# ASM001-design-2.net
KiCad netlist of a schematic drawn in Altium Designer
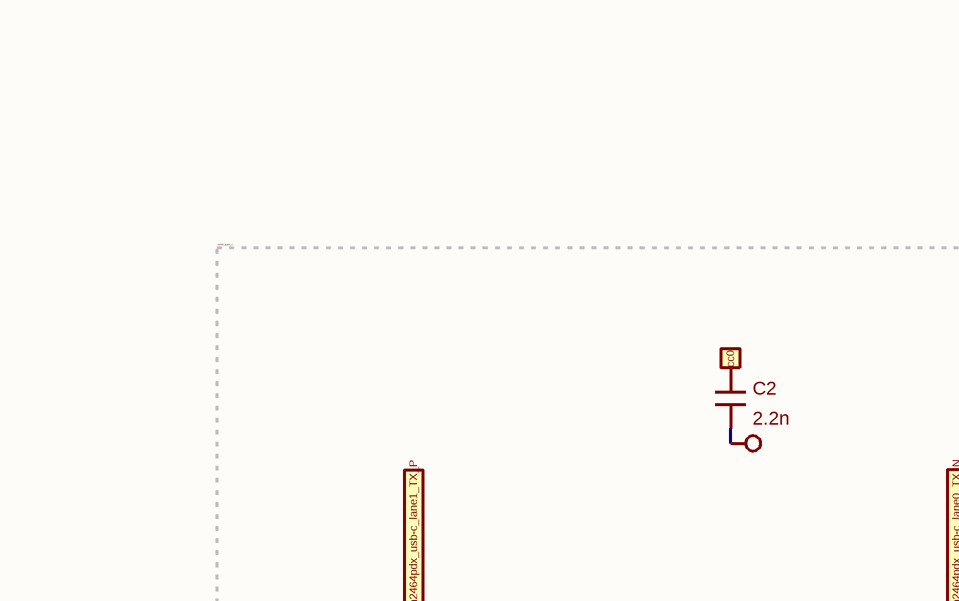
[diagram p0: ASM001-design-2.SchDoc, top column 1 of 4]
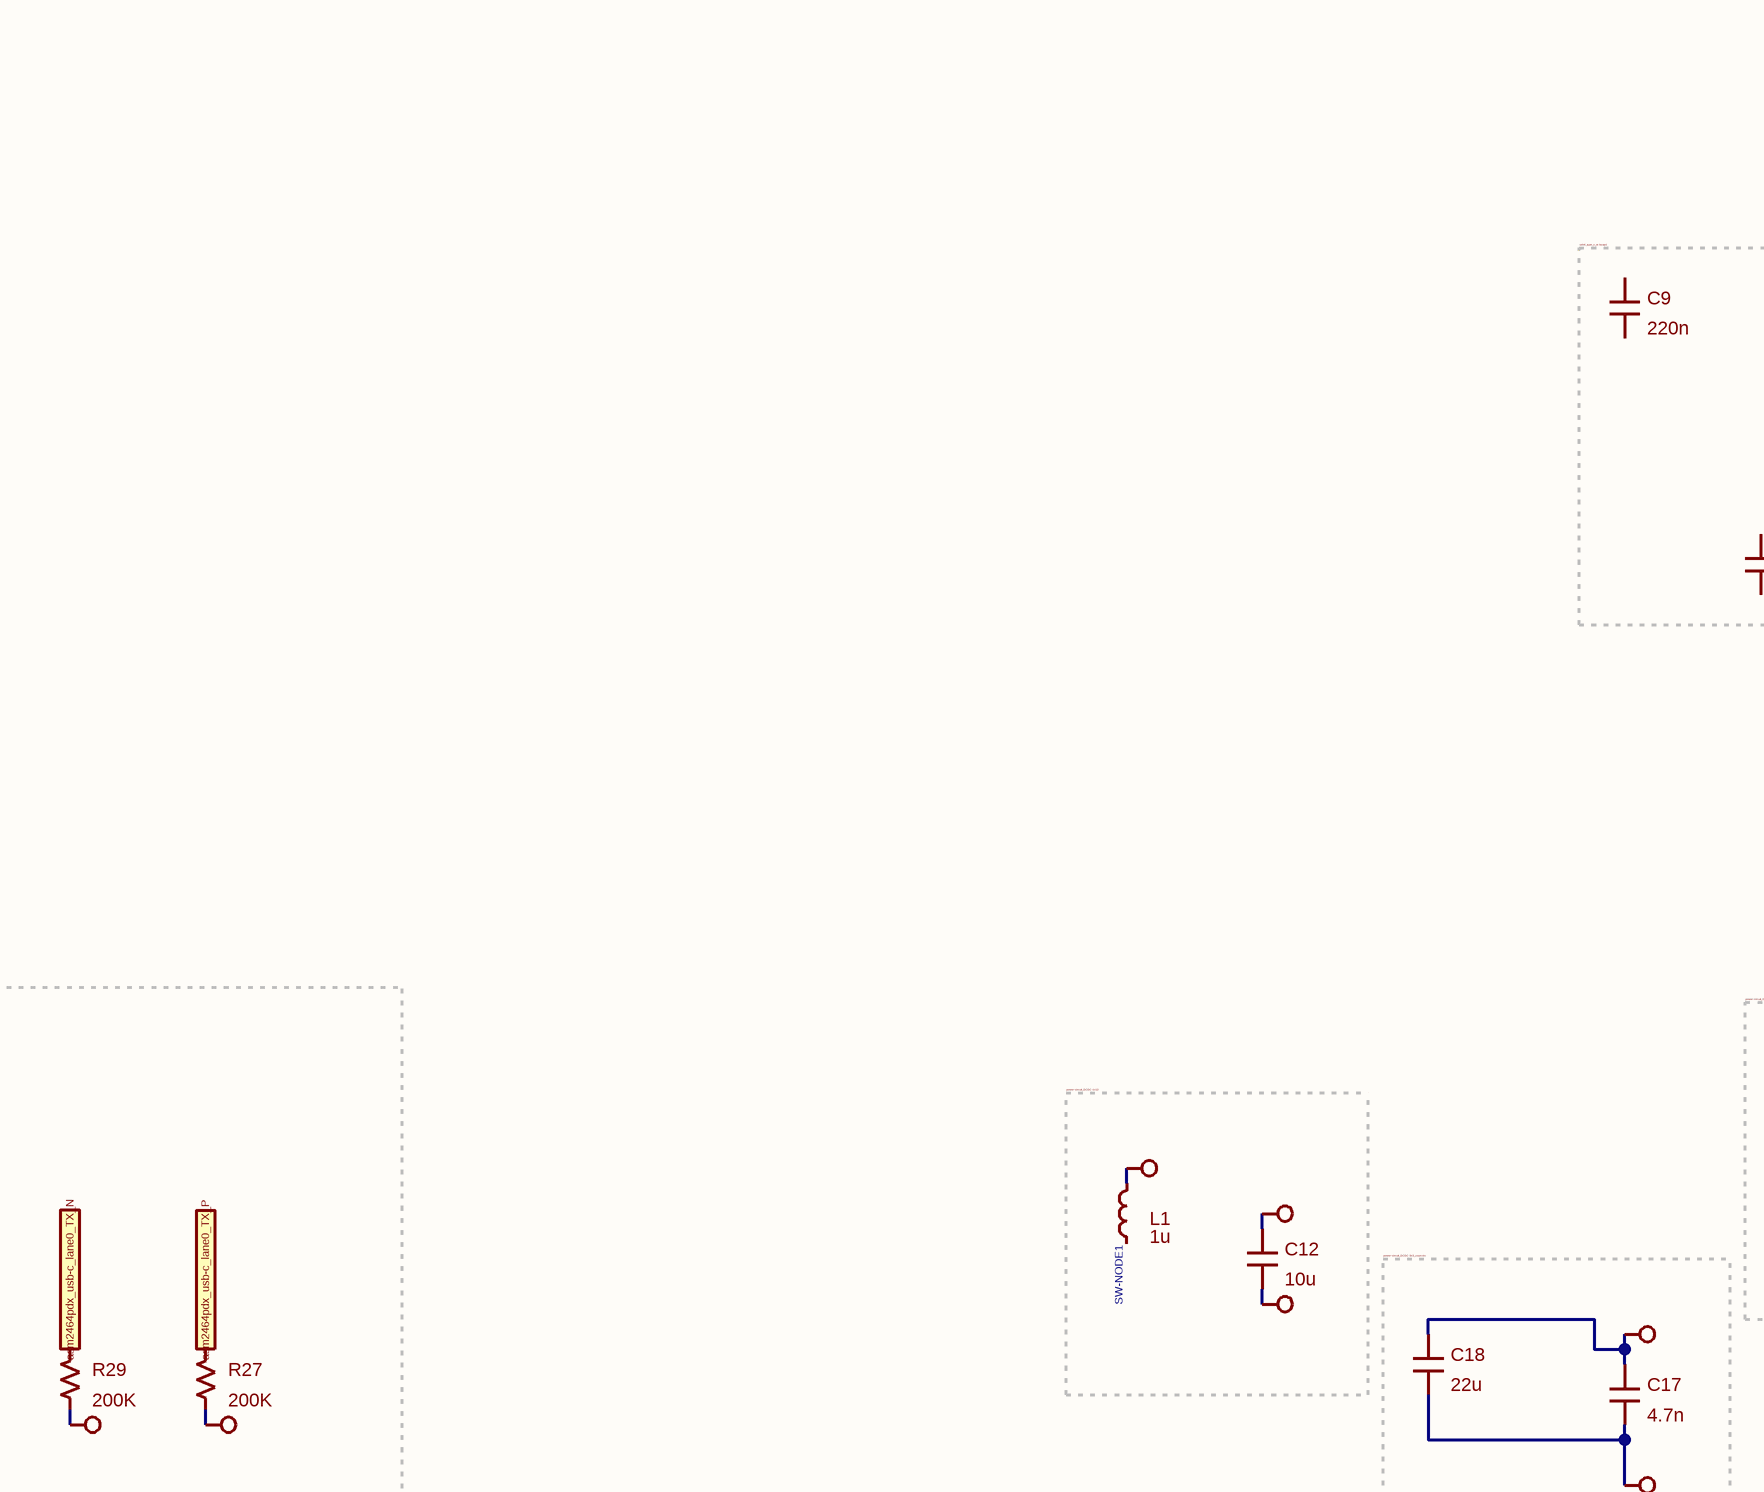
[diagram p1: ASM001-design-2.SchDoc, top column 2 of 4]
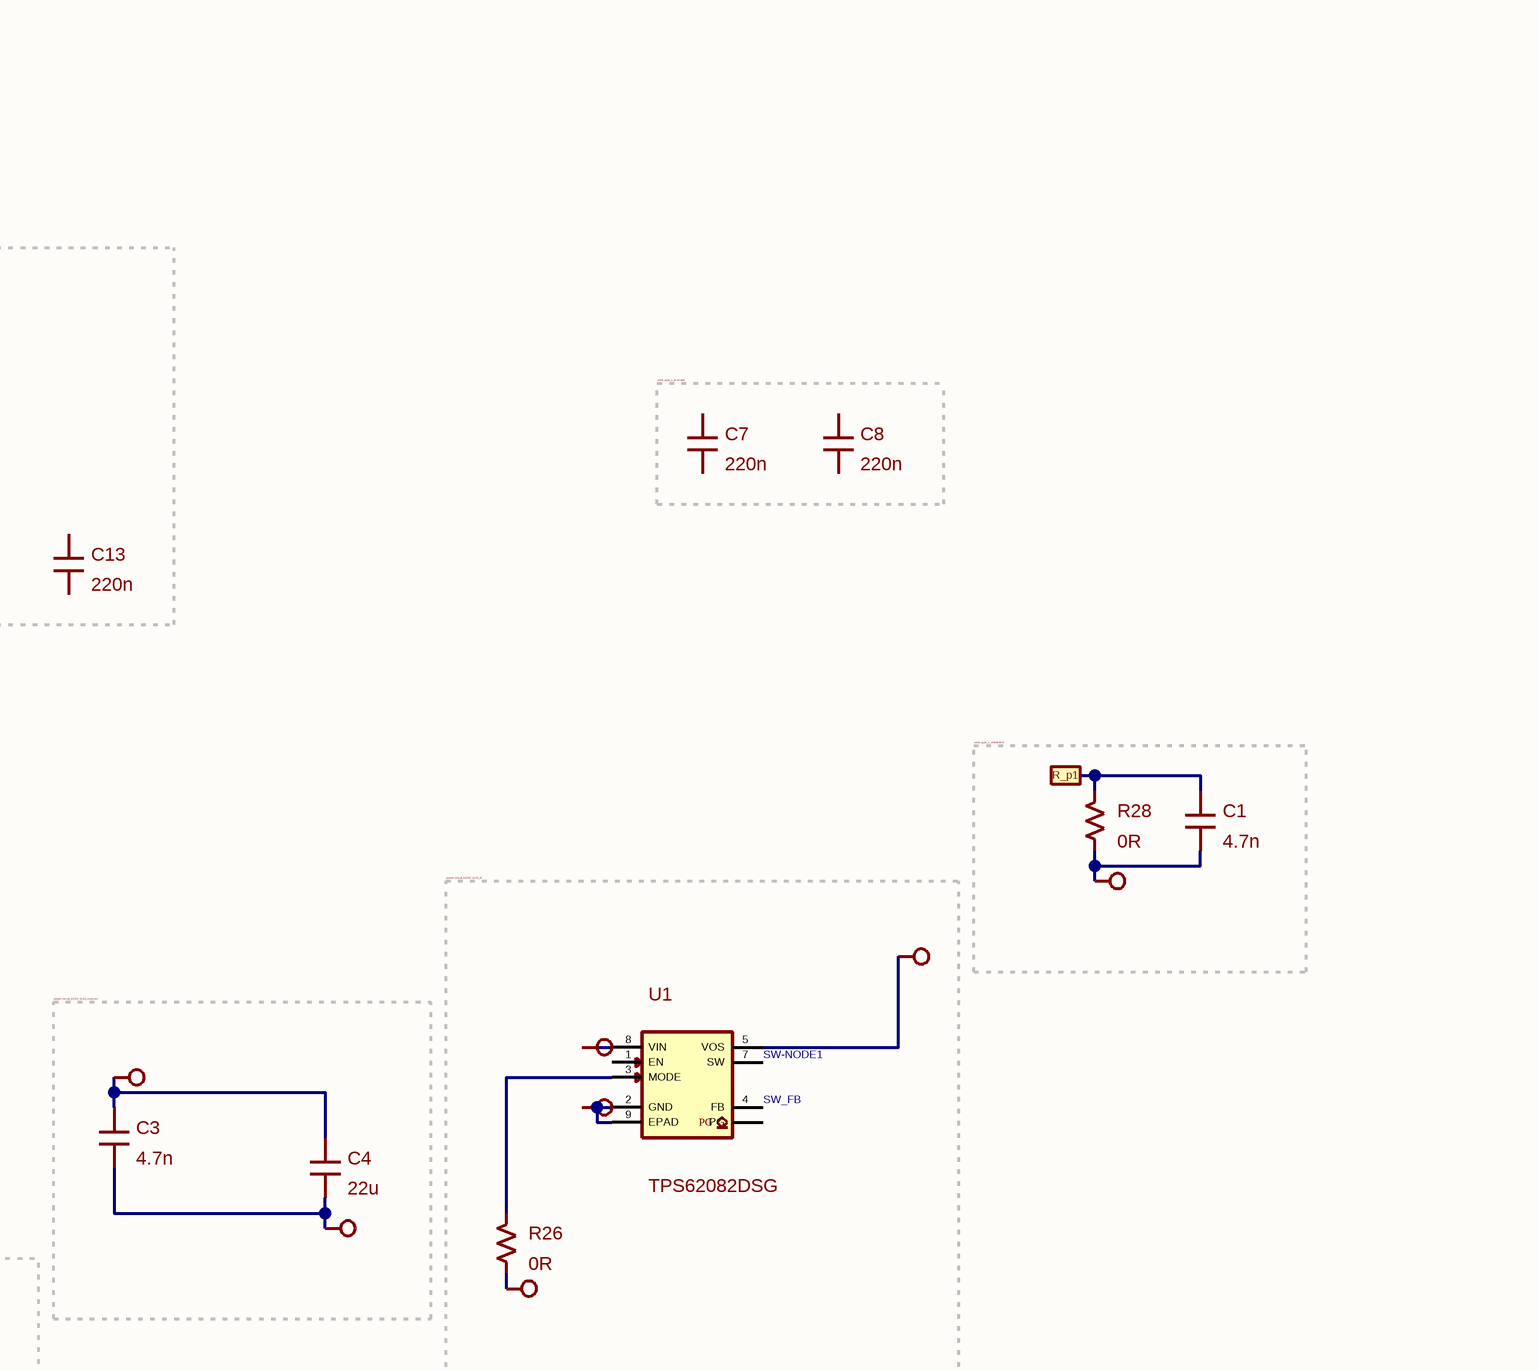
[diagram p2: ASM001-design-2.SchDoc, top column 3 of 4]
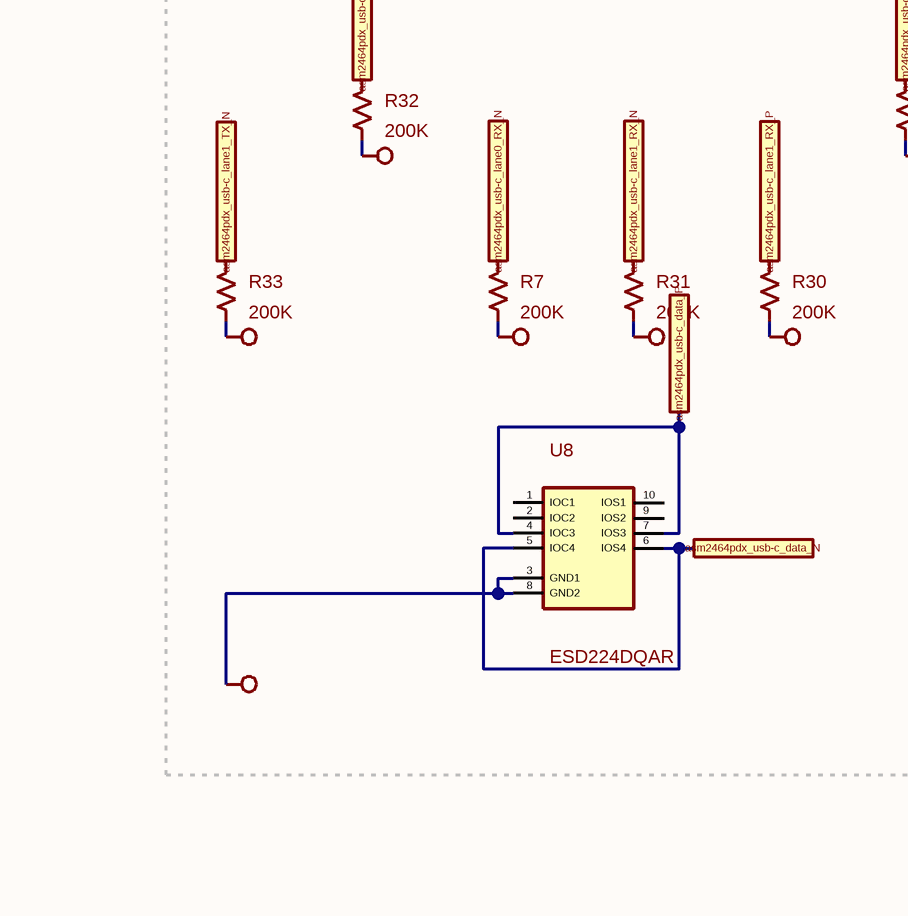
[diagram p3: ASM001-design-2.SchDoc, centre column 1 of 4]
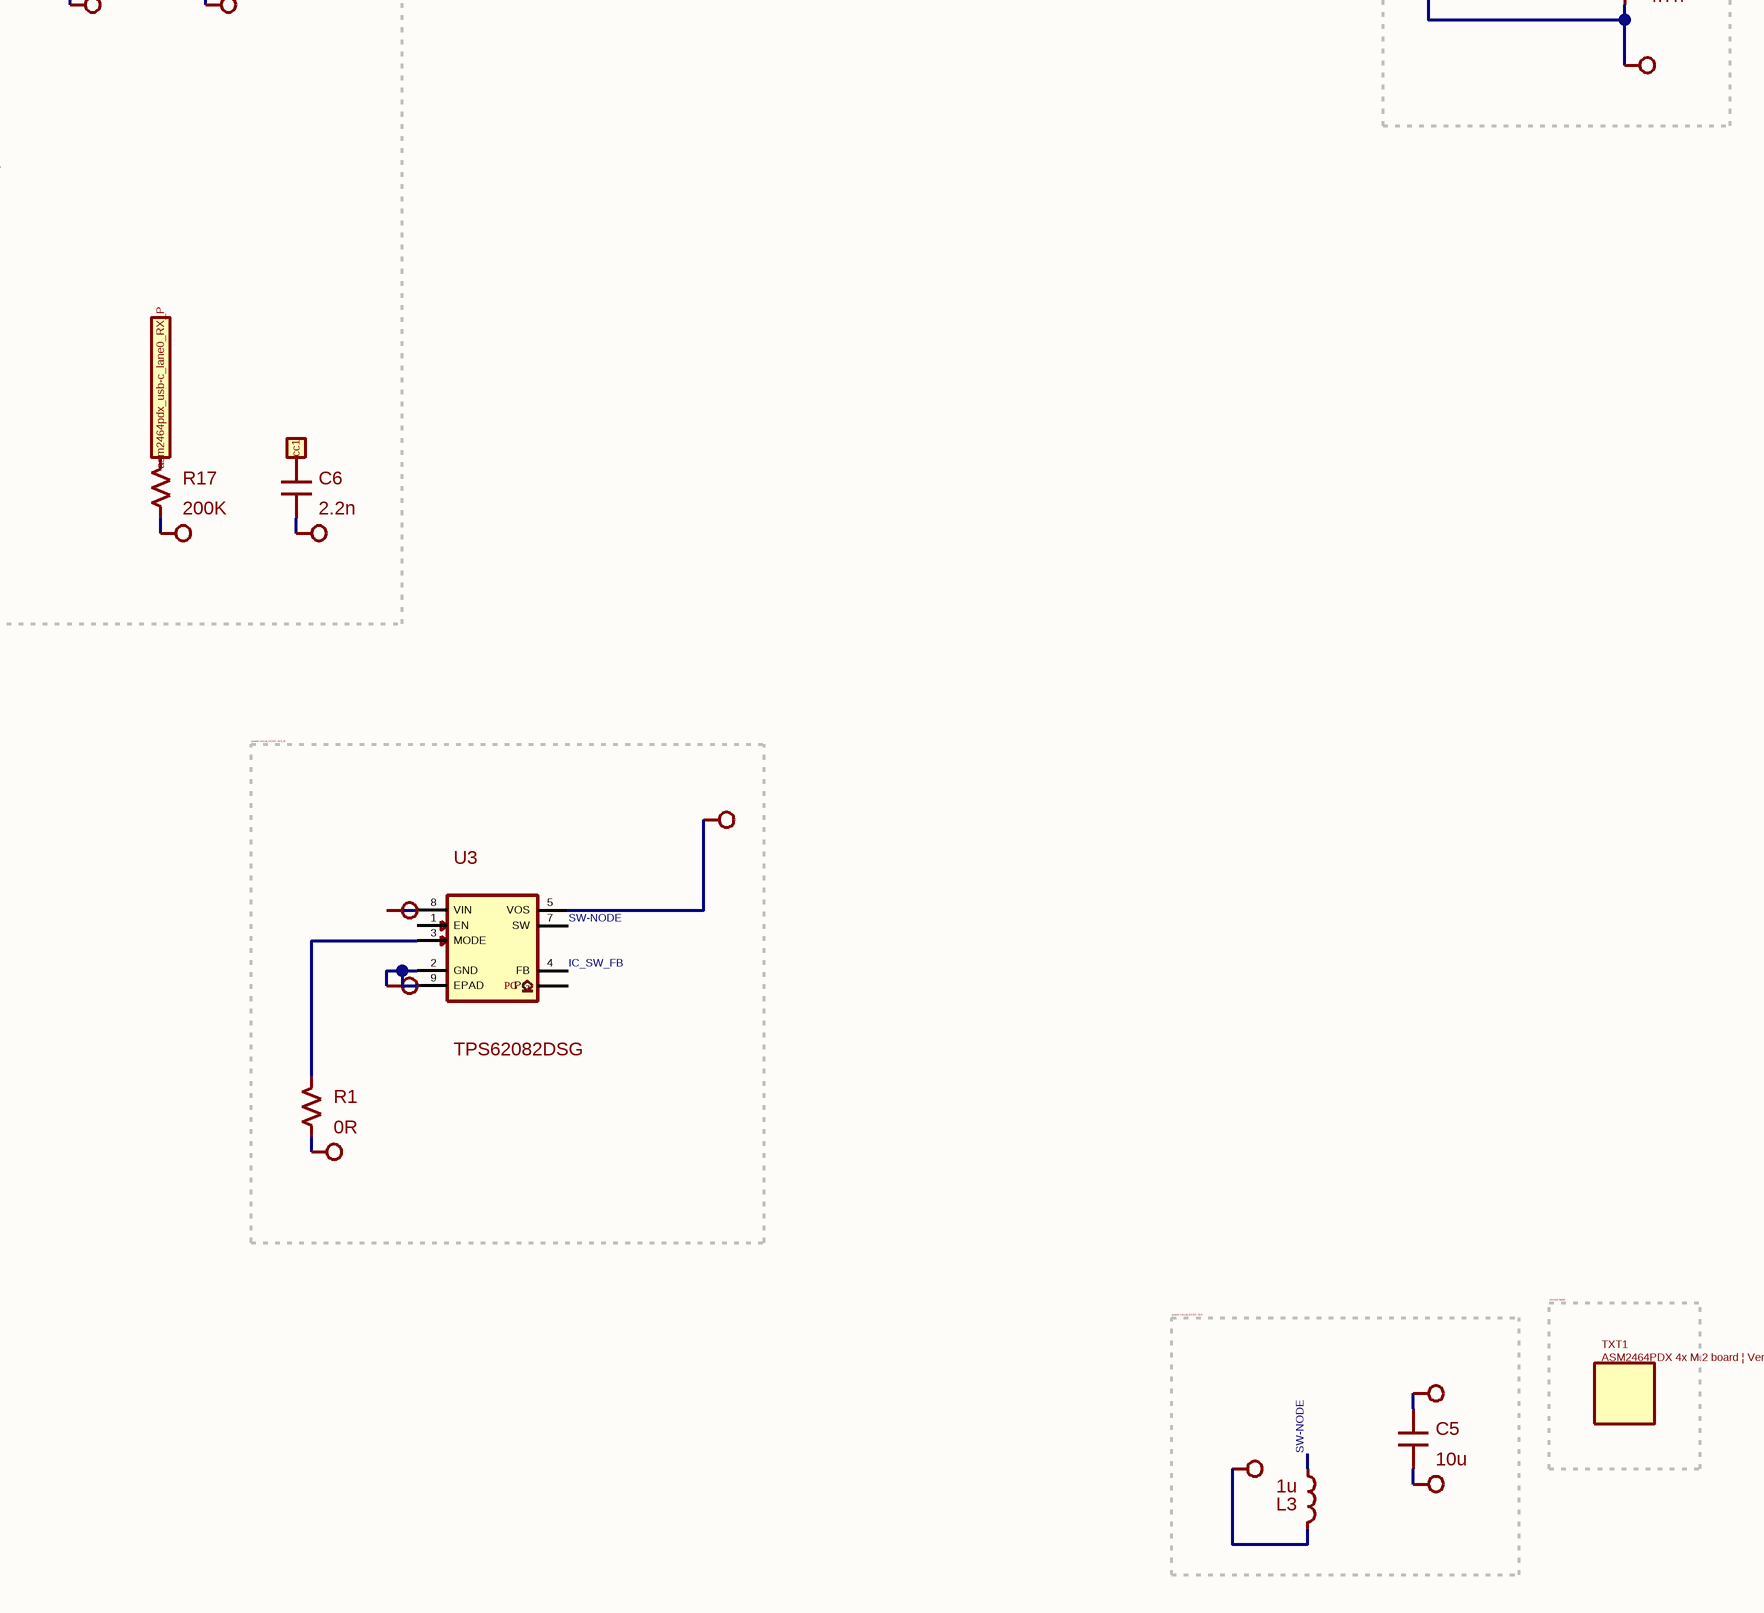
[diagram p4: ASM001-design-2.SchDoc, centre column 2 of 4]
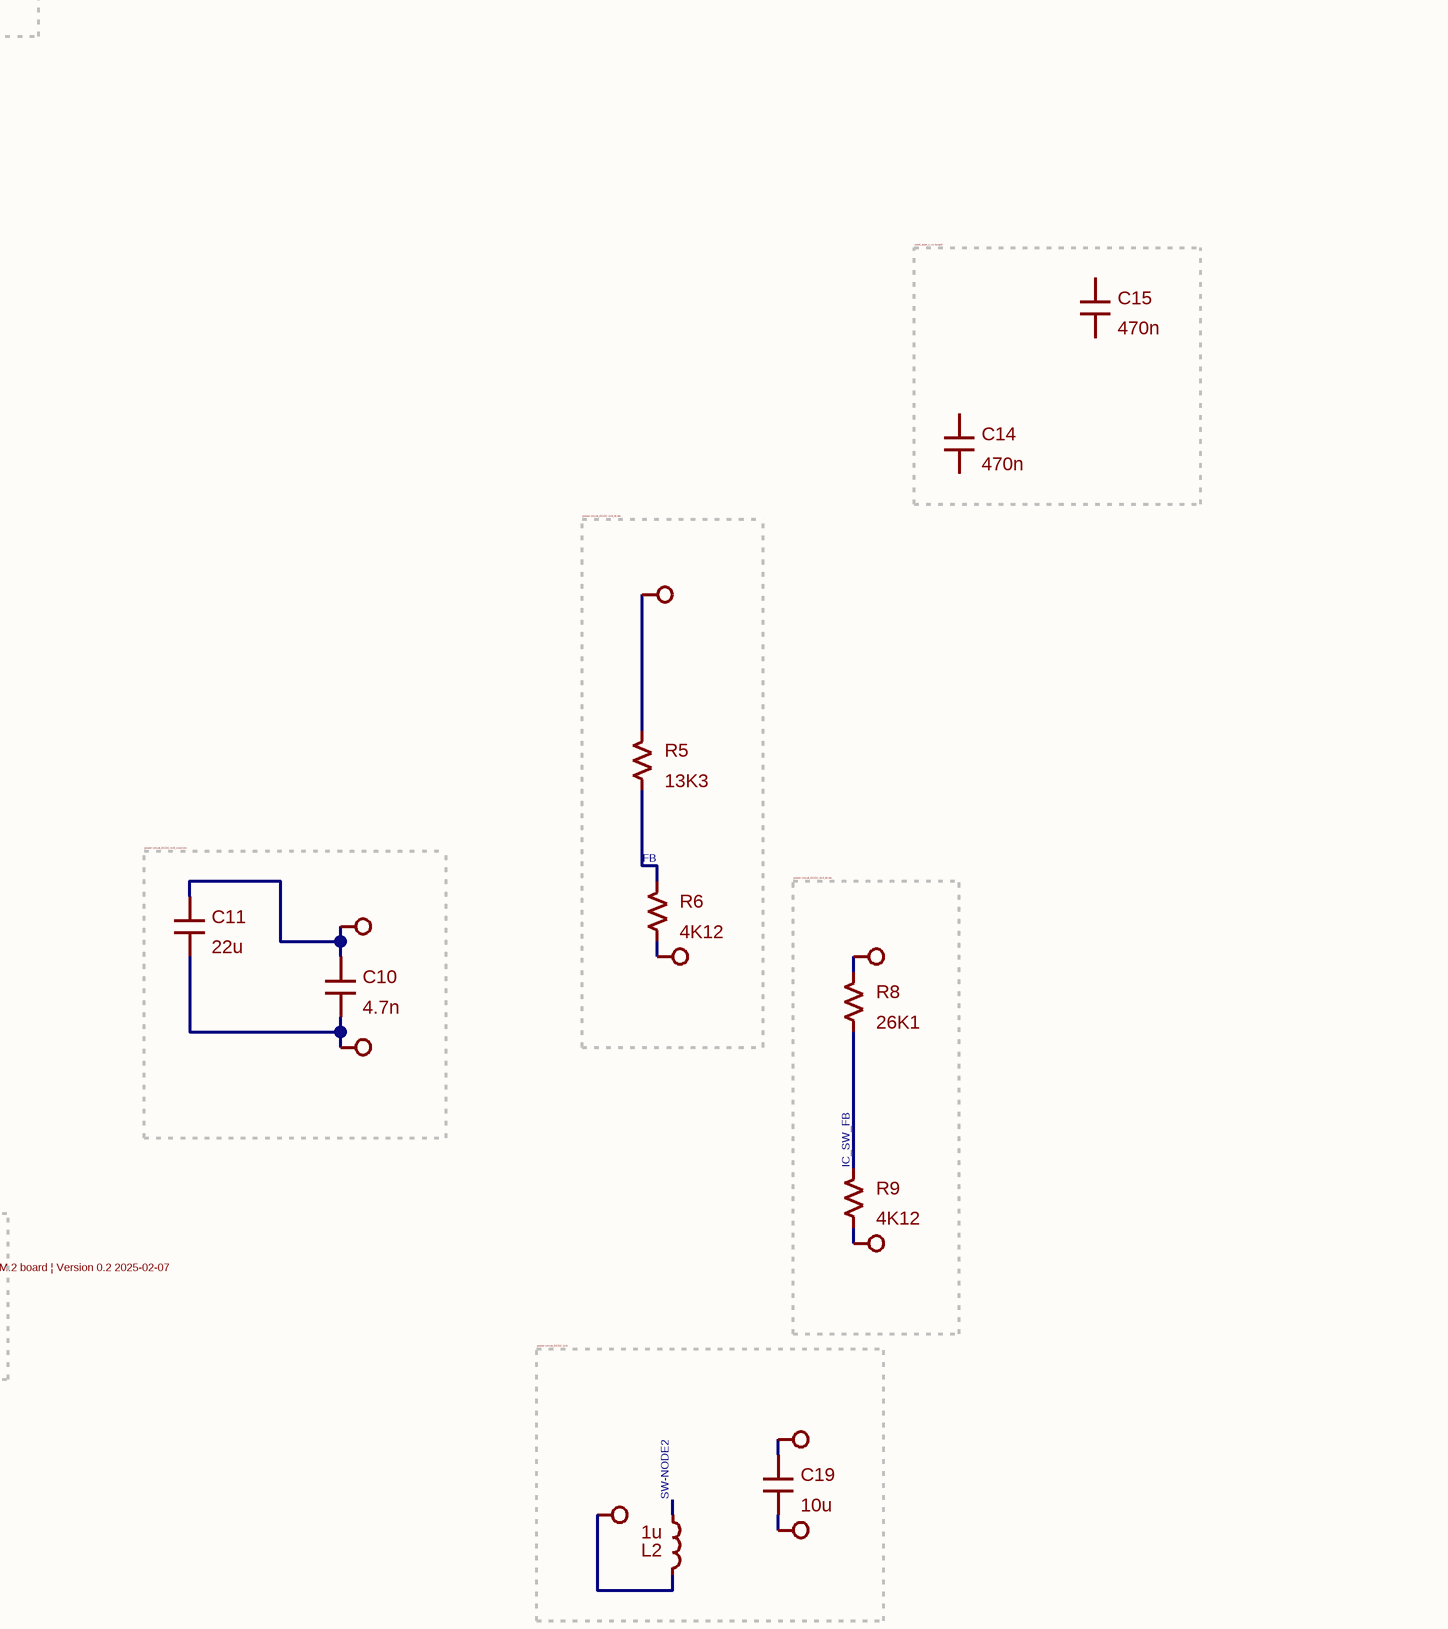
[diagram p5: ASM001-design-2.SchDoc, centre column 3 of 4]
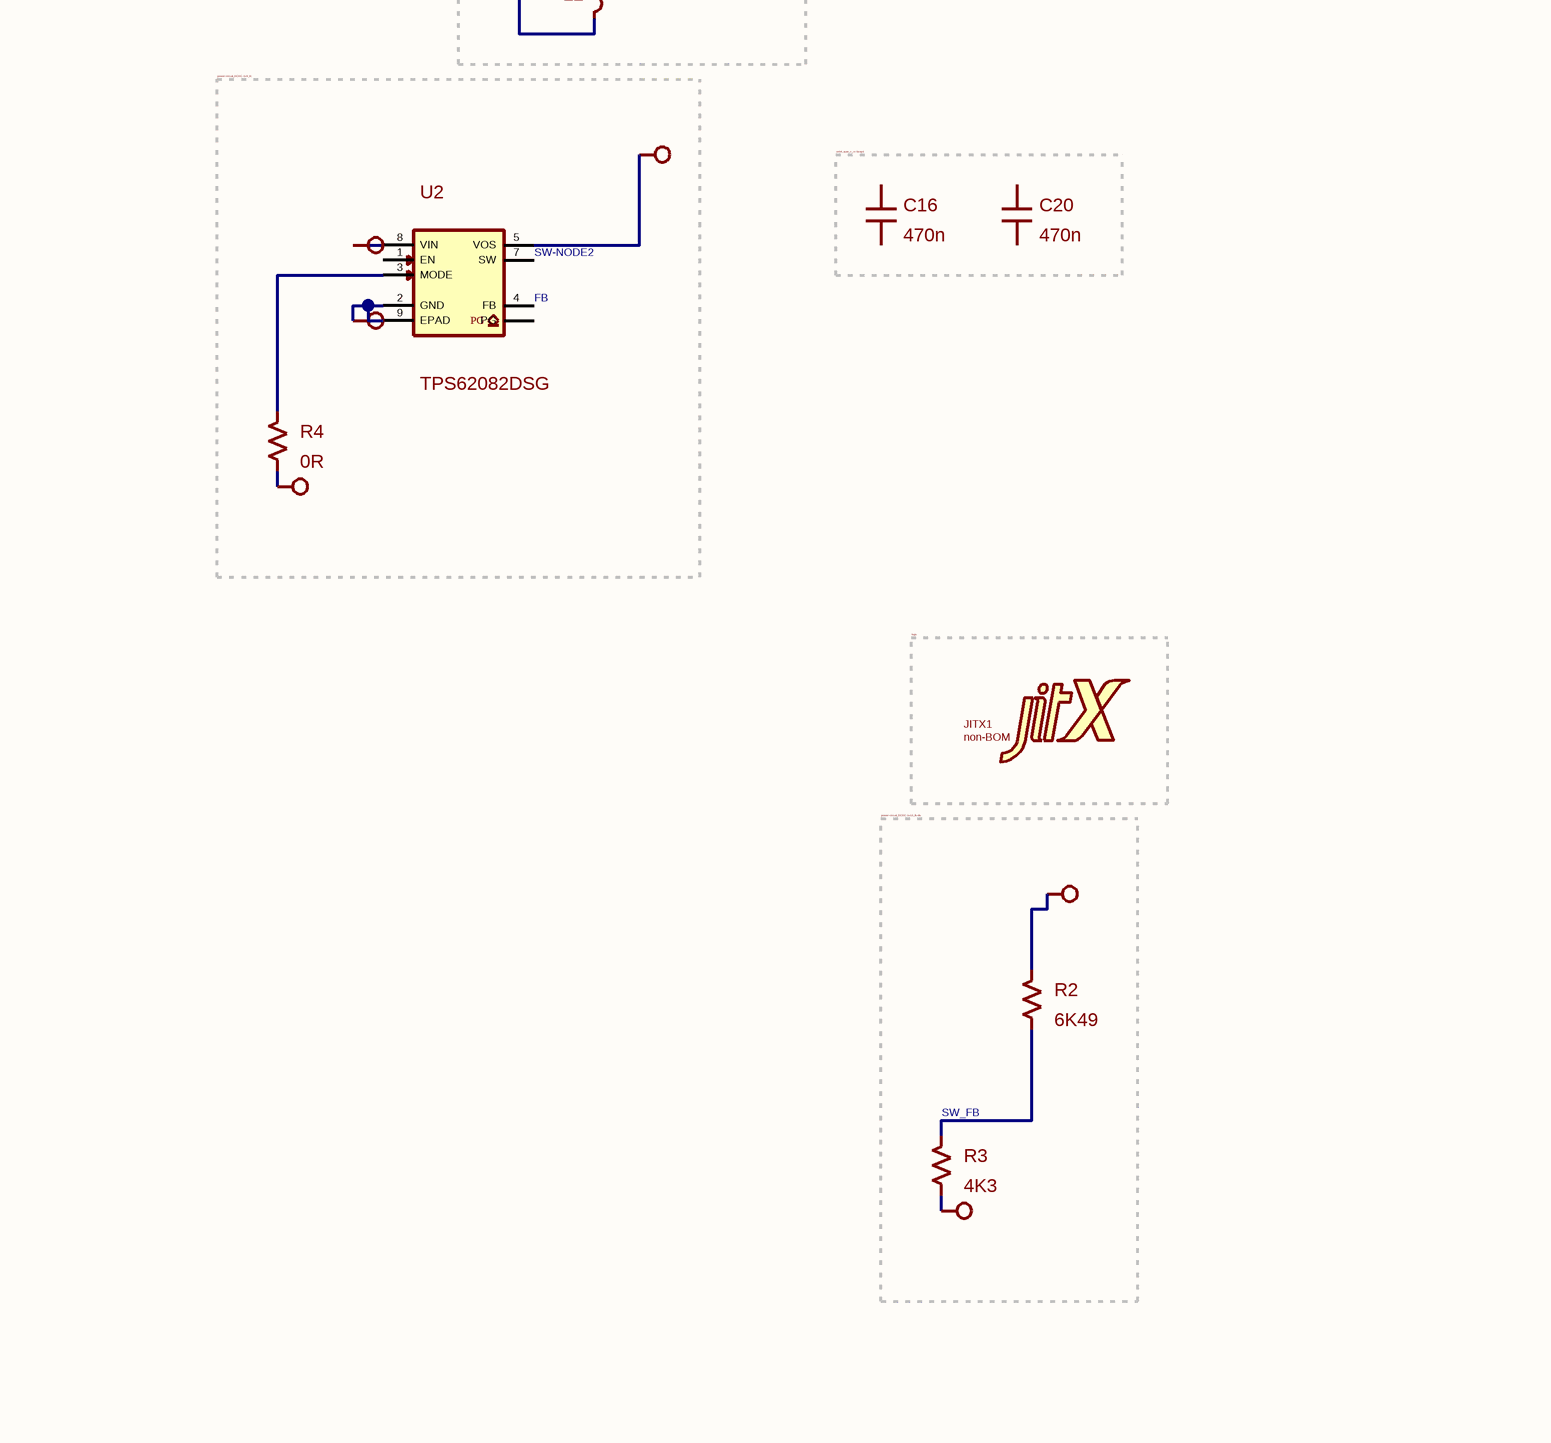
[diagram p6: ASM001-design-2.SchDoc, bottom column 3 of 4]
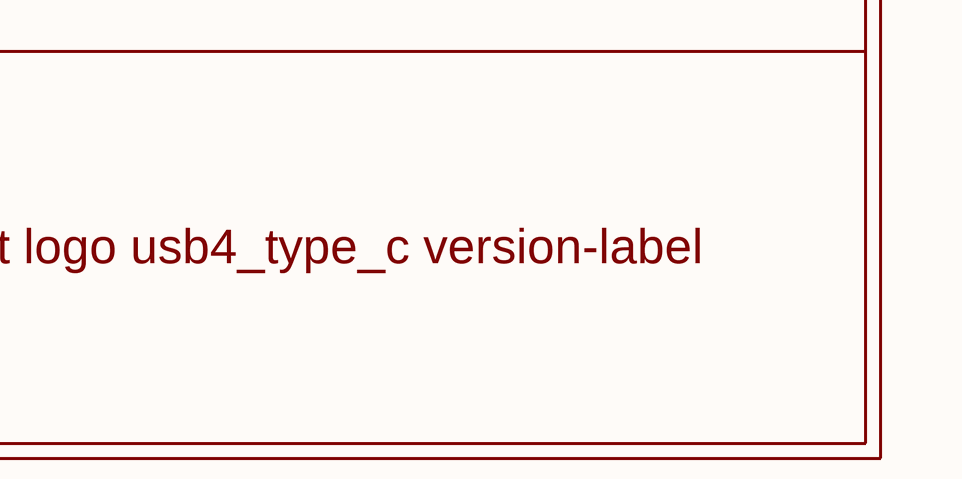
[diagram p7: ASM001-design-2.SchDoc, bottom column 4 of 4]

(export (version "E")
  (design (tool "Eeschema 10.0.6"))
  (components
    (comp (ref "C1")
      (value "4.7n")
      (footprint "Pkg0402$8")
      (description "C106208$1")
      (fields
        (field (name "TOLERANCE") "Toleranced(4.23e-009 <= 4.7e-009 <= 5.17e-009)")
        (field (name "MANUFACTURER") "YAGEO")
      )
      (libsource (lib "ASM001-design") (part "C106208$1"))
    )
    (comp (ref "C2")
      (value "2.2n")
      (footprint "Pkg0402$1")
      (description "C338130")
      (fields
        (field (name "TOLERANCE") "Toleranced(1.98e-009 <= 2.2e-009 <= 2.42e-009)")
        (field (name "MANUFACTURER") "Walsin Technology Corporation")
      )
      (libsource (lib "ASM001-design") (part "C338130"))
    )
    (comp (ref "C3")
      (value "4.7n")
      (footprint "Pkg0402$15")
      (description "C106208$2")
      (fields
        (field (name "TOLERANCE") "Toleranced(4.23e-009 <= 4.7e-009 <= 5.17e-009)")
        (field (name "MANUFACTURER") "YAGEO")
      )
      (libsource (lib "ASM001-design") (part "C106208$2"))
    )
    (comp (ref "C4")
      (value "22u")
      (footprint "Pkg0805")
      (description "C87997$1")
      (fields
        (field (name "TOLERANCE") "Toleranced(1.98e-005 <= 2.2e-005 <= 2.42e-005)")
        (field (name "MANUFACTURER") "Samsung Electro-Mechanics")
      )
      (libsource (lib "ASM001-design") (part "C87997$1"))
    )
    (comp (ref "C5")
      (value "10u")
      (footprint "Pkg0603$3")
      (description "C19702$2")
      (fields
        (field (name "TOLERANCE") "Toleranced(9.0e-006 <= 1.0e-005 <= 1.1e-005)")
        (field (name "MANUFACTURER") "Samsung Electro-Mechanics")
      )
      (libsource (lib "ASM001-design") (part "C19702$2"))
    )
    (comp (ref "C6")
      (value "2.2n")
      (footprint "Pkg0402$1")
      (description "C338130")
      (fields
        (field (name "TOLERANCE") "Toleranced(1.98e-009 <= 2.2e-009 <= 2.42e-009)")
        (field (name "MANUFACTURER") "Walsin Technology Corporation")
      )
      (libsource (lib "ASM001-design") (part "C338130"))
    )
    (comp (ref "C7")
      (value "220n")
      (footprint "Pkg0201")
      (description "C76931")
      (fields
        (field (name "TOLERANCE") "Toleranced(1.98e-007 <= 2.2e-007 <= 2.42e-007)")
        (field (name "MANUFACTURER") "Murata Electronics")
      )
      (libsource (lib "ASM001-design") (part "C76931"))
    )
    (comp (ref "C8")
      (value "220n")
      (footprint "Pkg0201")
      (description "C76931")
      (fields
        (field (name "TOLERANCE") "Toleranced(1.98e-007 <= 2.2e-007 <= 2.42e-007)")
        (field (name "MANUFACTURER") "Murata Electronics")
      )
      (libsource (lib "ASM001-design") (part "C76931"))
    )
    (comp (ref "C9")
      (value "220n")
      (footprint "Pkg0201")
      (description "C76931")
      (fields
        (field (name "TOLERANCE") "Toleranced(1.98e-007 <= 2.2e-007 <= 2.42e-007)")
        (field (name "MANUFACTURER") "Murata Electronics")
      )
      (libsource (lib "ASM001-design") (part "C76931"))
    )
    (comp (ref "C10")
      (value "4.7n")
      (footprint "Pkg0402$11")
      (description "C106208")
      (fields
        (field (name "TOLERANCE") "Toleranced(4.23e-009 <= 4.7e-009 <= 5.17e-009)")
        (field (name "MANUFACTURER") "YAGEO")
      )
      (libsource (lib "ASM001-design") (part "C106208"))
    )
    (comp (ref "C11")
      (value "22u")
      (footprint "Pkg0805$2")
      (description "C87997")
      (fields
        (field (name "TOLERANCE") "Toleranced(1.98e-005 <= 2.2e-005 <= 2.42e-005)")
        (field (name "MANUFACTURER") "Samsung Electro-Mechanics")
      )
      (libsource (lib "ASM001-design") (part "C87997"))
    )
    (comp (ref "C12")
      (value "10u")
      (footprint "Pkg0603$2")
      (description "C19702$1")
      (fields
        (field (name "TOLERANCE") "Toleranced(9.0e-006 <= 1.0e-005 <= 1.1e-005)")
        (field (name "MANUFACTURER") "Samsung Electro-Mechanics")
      )
      (libsource (lib "ASM001-design") (part "C19702$1"))
    )
    (comp (ref "C13")
      (value "220n")
      (footprint "Pkg0201")
      (description "C76931")
      (fields
        (field (name "TOLERANCE") "Toleranced(1.98e-007 <= 2.2e-007 <= 2.42e-007)")
        (field (name "MANUFACTURER") "Murata Electronics")
      )
      (libsource (lib "ASM001-design") (part "C76931"))
    )
    (comp (ref "C14")
      (value "470n")
      (footprint "Pkg0201$3")
      (description "C85926")
      (fields
        (field (name "TOLERANCE") "Toleranced(4.23e-007 <= 4.7e-007 <= 5.17e-007)")
        (field (name "MANUFACTURER") "Murata Electronics")
      )
      (libsource (lib "ASM001-design") (part "C85926"))
    )
    (comp (ref "C15")
      (value "470n")
      (footprint "Pkg0201$3")
      (description "C85926")
      (fields
        (field (name "TOLERANCE") "Toleranced(4.23e-007 <= 4.7e-007 <= 5.17e-007)")
        (field (name "MANUFACTURER") "Murata Electronics")
      )
      (libsource (lib "ASM001-design") (part "C85926"))
    )
    (comp (ref "C16")
      (value "470n")
      (footprint "Pkg0201$3")
      (description "C85926")
      (fields
        (field (name "TOLERANCE") "Toleranced(4.23e-007 <= 4.7e-007 <= 5.17e-007)")
        (field (name "MANUFACTURER") "Murata Electronics")
      )
      (libsource (lib "ASM001-design") (part "C85926"))
    )
    (comp (ref "C17")
      (value "4.7n")
      (footprint "Pkg0402$4")
      (description "C106208$3")
      (fields
        (field (name "TOLERANCE") "Toleranced(4.23e-009 <= 4.7e-009 <= 5.17e-009)")
        (field (name "MANUFACTURER") "YAGEO")
      )
      (libsource (lib "ASM001-design") (part "C106208$3"))
    )
    (comp (ref "C18")
      (value "22u")
      (footprint "Pkg0805$1")
      (description "C87997$2")
      (fields
        (field (name "TOLERANCE") "Toleranced(1.98e-005 <= 2.2e-005 <= 2.42e-005)")
        (field (name "MANUFACTURER") "Samsung Electro-Mechanics")
      )
      (libsource (lib "ASM001-design") (part "C87997$2"))
    )
    (comp (ref "C19")
      (value "10u")
      (footprint "Pkg0603$1")
      (description "C19702")
      (fields
        (field (name "TOLERANCE") "Toleranced(9.0e-006 <= 1.0e-005 <= 1.1e-005)")
        (field (name "MANUFACTURER") "Samsung Electro-Mechanics")
      )
      (libsource (lib "ASM001-design") (part "C19702"))
    )
    (comp (ref "C20")
      (value "470n")
      (footprint "Pkg0201$3")
      (description "C85926")
      (fields
        (field (name "TOLERANCE") "Toleranced(4.23e-007 <= 4.7e-007 <= 5.17e-007)")
        (field (name "MANUFACTURER") "Murata Electronics")
      )
      (libsource (lib "ASM001-design") (part "C85926"))
    )
    (comp (ref "JITX1")
      (value "non-BOM")
      (footprint "JITX_SM_LP")
      (description "JITX")
      (libsource (lib "ASM001-design") (part "JITX"))
    )
    (comp (ref "L1")
      (value "1u")
      (footprint "MOLDED")
      (description "component$3")
      (fields (field (name "TOLERANCE") "0.2%") (field (name "MPN") "XFL3012-102MEC"))
      (libsource (lib "ASM001-design") (part "component$3"))
    )
    (comp (ref "L2")
      (value "1u")
      (footprint "MOLDED")
      (description "component$3")
      (fields (field (name "TOLERANCE") "0.2%") (field (name "MPN") "XFL3012-102MEC"))
      (libsource (lib "ASM001-design") (part "component$3"))
    )
    (comp (ref "L3")
      (value "1u")
      (footprint "MOLDED")
      (description "component$3")
      (fields (field (name "TOLERANCE") "0.2%") (field (name "MPN") "XFL3012-102MEC"))
      (libsource (lib "ASM001-design") (part "component$3"))
    )
    (comp (ref "R1")
      (value "0R")
      (footprint "Pkg0402$16")
      (description "my_resistor$4")
      (fields
        (field (name "MPN") "SC0402F0000I2ANRH")
        (field (name "TOLERANCE") "Toleranced(0.0 <= 0.0 <= 0.0)")
      )
      (libsource (lib "ASM001-design") (part "my_resistor$4"))
    )
    (comp (ref "R2")
      (value "6K49")
      (footprint "Pkg0402$14")
      (description "C364360")
      (fields
        (field (name "TOLERANCE") "Toleranced(6425.1 <= 6490.0 <= 6554.9)")
        (field (name "MANUFACTURER") "YAGEO")
      )
      (libsource (lib "ASM001-design") (part "C364360"))
    )
    (comp (ref "R3")
      (value "4K3")
      (footprint "Pkg0402")
      (description "my_resistor$9")
      (fields
        (field (name "MPN") "FRC0402F4301TS")
        (field (name "TOLERANCE") "Toleranced(4257.0 <= 4300.0 <= 4343.0)")
      )
      (libsource (lib "ASM001-design") (part "my_resistor$9"))
    )
    (comp (ref "R4")
      (value "0R")
      (footprint "Pkg0402$6")
      (description "my_resistor$1")
      (fields
        (field (name "MPN") "SC0402F0000I2ANRH")
        (field (name "TOLERANCE") "Toleranced(0.0 <= 0.0 <= 0.0)")
      )
      (libsource (lib "ASM001-design") (part "my_resistor$1"))
    )
    (comp (ref "R5")
      (value "13K3")
      (footprint "Pkg0402$9")
      (description "C334647")
      (fields
        (field (name "TOLERANCE") "Toleranced(13167.0 <= 13300.0 <= 13433.0)")
        (field (name "MANUFACTURER") "Walsin Technology Corporation")
      )
      (libsource (lib "ASM001-design") (part "C334647"))
    )
    (comp (ref "R6")
      (value "4K12")
      (footprint "Pkg0402$13")
      (description "C327340")
      (fields
        (field (name "TOLERANCE") "Toleranced(4078.8 <= 4120.0 <= 4161.2)")
        (field (name "MANUFACTURER") "YAGEO")
      )
      (libsource (lib "ASM001-design") (part "C327340"))
    )
    (comp (ref "R7")
      (value "200K")
      (footprint "Pkg0201$1")
      (description "my_resistor")
      (fields
        (field (name "MPN") "SC0201F2003G1BNRH")
        (field (name "TOLERANCE") "Toleranced(198000.0 <= 200000.0 <= 202000.0)")
      )
      (libsource (lib "ASM001-design") (part "my_resistor"))
    )
    (comp (ref "R8")
      (value "26K1")
      (footprint "Pkg0603")
      (description "my_resistor$3")
      (fields
        (field (name "TOLERANCE") "Toleranced(26073.9 <= 26100.0 <= 26126.1)")
        (field (name "MANUFACTURER") "YAGEO")
      )
      (libsource (lib "ASM001-design") (part "my_resistor$3"))
    )
    (comp (ref "R9")
      (value "4K12")
      (footprint "Pkg0402$7")
      (description "my_resistor$6")
      (fields
        (field (name "TOLERANCE") "Toleranced(4115.88 <= 4120.0 <= 4124.12)")
        (field (name "MANUFACTURER") "YAGEO")
      )
      (libsource (lib "ASM001-design") (part "my_resistor$6"))
    )
    (comp (ref "R17")
      (value "200K")
      (footprint "Pkg0201$1")
      (description "my_resistor")
      (fields
        (field (name "MPN") "SC0201F2003G1BNRH")
        (field (name "TOLERANCE") "Toleranced(198000.0 <= 200000.0 <= 202000.0)")
      )
      (libsource (lib "ASM001-design") (part "my_resistor"))
    )
    (comp (ref "R26")
      (value "0R")
      (footprint "Pkg0402$12")
      (description "my_resistor$5")
      (fields
        (field (name "MPN") "SC0402F0000I2ANRH")
        (field (name "TOLERANCE") "Toleranced(0.0 <= 0.0 <= 0.0)")
      )
      (libsource (lib "ASM001-design") (part "my_resistor$5"))
    )
    (comp (ref "R27")
      (value "200K")
      (footprint "Pkg0201$1")
      (description "my_resistor")
      (fields
        (field (name "MPN") "SC0201F2003G1BNRH")
        (field (name "TOLERANCE") "Toleranced(198000.0 <= 200000.0 <= 202000.0)")
      )
      (libsource (lib "ASM001-design") (part "my_resistor"))
    )
    (comp (ref "R28")
      (value "0R")
      (footprint "Pkg0402$3")
      (description "my_resistor$2")
      (fields
        (field (name "MPN") "SC0402F0000I2ANRH")
        (field (name "TOLERANCE") "Toleranced(0.0 <= 0.0 <= 0.0)")
      )
      (libsource (lib "ASM001-design") (part "my_resistor$2"))
    )
    (comp (ref "R29")
      (value "200K")
      (footprint "Pkg0201$1")
      (description "my_resistor")
      (fields
        (field (name "MPN") "SC0201F2003G1BNRH")
        (field (name "TOLERANCE") "Toleranced(198000.0 <= 200000.0 <= 202000.0)")
      )
      (libsource (lib "ASM001-design") (part "my_resistor"))
    )
    (comp (ref "R30")
      (value "200K")
      (footprint "Pkg0201$1")
      (description "my_resistor")
      (fields
        (field (name "MPN") "SC0201F2003G1BNRH")
        (field (name "TOLERANCE") "Toleranced(198000.0 <= 200000.0 <= 202000.0)")
      )
      (libsource (lib "ASM001-design") (part "my_resistor"))
    )
    (comp (ref "R31")
      (value "200K")
      (footprint "Pkg0201$1")
      (description "my_resistor")
      (fields
        (field (name "MPN") "SC0201F2003G1BNRH")
        (field (name "TOLERANCE") "Toleranced(198000.0 <= 200000.0 <= 202000.0)")
      )
      (libsource (lib "ASM001-design") (part "my_resistor"))
    )
    (comp (ref "R32")
      (value "200K")
      (footprint "Pkg0201$1")
      (description "my_resistor")
      (fields
        (field (name "MPN") "SC0201F2003G1BNRH")
        (field (name "TOLERANCE") "Toleranced(198000.0 <= 200000.0 <= 202000.0)")
      )
      (libsource (lib "ASM001-design") (part "my_resistor"))
    )
    (comp (ref "R33")
      (value "200K")
      (footprint "Pkg0201$1")
      (description "my_resistor")
      (fields
        (field (name "MPN") "SC0201F2003G1BNRH")
        (field (name "TOLERANCE") "Toleranced(198000.0 <= 200000.0 <= 202000.0)")
      )
      (libsource (lib "ASM001-design") (part "my_resistor"))
    )
    (comp (ref "TXT1")
      (value "ASM2464PDX 4x M.2 board ¦ Version 0.2 2025-02-07")
      (footprint "TEXT_LP")
      (description "ASM2464PDX_4x_M_2_board___Version_0_2_2025_02_07")
      (fields (field (name "MANUFACTURER") "non-BOM"))
      (libsource (lib "ASM001-design") (part "ASM2464PDX_4x_M_2_board___Version_0_2_2025_02_07"))
    )
    (comp (ref "U1")
      (value "TPS62082DSG")
      (footprint "SON50P200X200_9N")
      (description "component$1")
      (fields (field (name "MANUFACTURER") "Texas Instruments"))
      (libsource (lib "ASM001-design") (part "component$1"))
    )
    (comp (ref "U2")
      (value "TPS62082DSG")
      (footprint "SON50P200X200_9N")
      (description "component$1")
      (fields (field (name "MANUFACTURER") "Texas Instruments"))
      (libsource (lib "ASM001-design") (part "component$1"))
    )
    (comp (ref "U3")
      (value "TPS62082DSG")
      (footprint "SON50P200X200_9N")
      (description "component$1")
      (fields (field (name "MANUFACTURER") "Texas Instruments"))
      (libsource (lib "ASM001-design") (part "component$1"))
    )
    (comp (ref "U8")
      (value "ESD224DQAR")
      (footprint "USON_10")
      (description "device")
      (fields (field (name "MANUFACTURER") "Texas Instruments"))
      (libsource (lib "ASM001-design") (part "device"))
    )
  )
  (nets
    (net (code "1") (name "/FB") (class "Default")
      (node (ref "R5") (pin "2") (pinfunction "2_2") (pintype "passive"))
      (node (ref "R6") (pin "1") (pinfunction "1_1") (pintype "passive"))
      (node (ref "U2") (pin "4") (pinfunction "FB_4") (pintype "passive"))
    )
    (net (code "2") (name "/IC_SW_FB") (class "Default")
      (node (ref "R8") (pin "2") (pinfunction "2_2") (pintype "passive"))
      (node (ref "R9") (pin "1") (pinfunction "1_1") (pintype "passive"))
      (node (ref "U3") (pin "4") (pinfunction "FB_4") (pintype "passive"))
    )
    (net (code "3") (name "/R_p1") (class "Default")
      (node (ref "C1") (pin "1") (pinfunction "1_1") (pintype "passive"))
      (node (ref "R28") (pin "1") (pinfunction "1_1") (pintype "passive"))
    )
    (net (code "4") (name "/SW-NODE") (class "Default")
      (node (ref "L3") (pin "c") (pinfunction "c_c") (pintype "passive"))
      (node (ref "U3") (pin "7") (pinfunction "SW_7") (pintype "passive"))
    )
    (net (code "5") (name "/SW-NODE1") (class "Default")
      (node (ref "L1") (pin "c") (pinfunction "c_c") (pintype "passive"))
      (node (ref "U1") (pin "7") (pinfunction "SW_7") (pintype "passive"))
    )
    (net (code "6") (name "/SW-NODE2") (class "Default")
      (node (ref "L2") (pin "c") (pinfunction "c_c") (pintype "passive"))
      (node (ref "U2") (pin "7") (pinfunction "SW_7") (pintype "passive"))
    )
    (net (code "7") (name "/SW_FB") (class "Default")
      (node (ref "R2") (pin "2") (pinfunction "2_2") (pintype "passive"))
      (node (ref "R3") (pin "1") (pinfunction "1_1") (pintype "passive"))
      (node (ref "U1") (pin "4") (pinfunction "FB_4") (pintype "passive"))
    )
    (net (code "8") (name "/asm2464pdx_usb-c_data_N") (class "Default")
      (node (ref "U8") (pin "5") (pinfunction "IOC4_5") (pintype "passive"))
      (node (ref "U8") (pin "6") (pinfunction "IOS4_6") (pintype "passive"))
    )
    (net (code "9") (name "/asm2464pdx_usb-c_data_P") (class "Default")
      (node (ref "U8") (pin "4") (pinfunction "IOC3_4") (pintype "passive"))
      (node (ref "U8") (pin "7") (pinfunction "IOS3_7") (pintype "passive"))
    )
    (net (code "10") (name "/asm2464pdx_usb-c_lane0_RX_N") (class "Default")
      (node (ref "R7") (pin "1") (pinfunction "1_1") (pintype "passive"))
    )
    (net (code "11") (name "/asm2464pdx_usb-c_lane0_RX_P") (class "Default")
      (node (ref "R17") (pin "1") (pinfunction "1_1") (pintype "passive"))
    )
    (net (code "12") (name "/asm2464pdx_usb-c_lane0_TX_N") (class "Default")
      (node (ref "R29") (pin "1") (pinfunction "1_1") (pintype "passive"))
    )
    (net (code "13") (name "/asm2464pdx_usb-c_lane0_TX_P") (class "Default")
      (node (ref "R27") (pin "1") (pinfunction "1_1") (pintype "passive"))
    )
    (net (code "14") (name "/asm2464pdx_usb-c_lane1_RX_N") (class "Default")
      (node (ref "R31") (pin "1") (pinfunction "1_1") (pintype "passive"))
    )
    (net (code "15") (name "/asm2464pdx_usb-c_lane1_RX_P") (class "Default")
      (node (ref "R30") (pin "1") (pinfunction "1_1") (pintype "passive"))
    )
    (net (code "16") (name "/asm2464pdx_usb-c_lane1_TX_N") (class "Default")
      (node (ref "R33") (pin "1") (pinfunction "1_1") (pintype "passive"))
    )
    (net (code "17") (name "/asm2464pdx_usb-c_lane1_TX_P") (class "Default")
      (node (ref "R32") (pin "1") (pinfunction "1_1") (pintype "passive"))
    )
    (net (code "18") (name "/cc0") (class "Default")
      (node (ref "C2") (pin "1") (pinfunction "1_1") (pintype "passive"))
    )
    (net (code "19") (name "/cc1") (class "Default")
      (node (ref "C6") (pin "1") (pinfunction "1_1") (pintype "passive"))
    )
    (net (code "20") (name "<NO NET>") (class "Default")
      (node (ref "C1") (pin "2") (pinfunction "2_2") (pintype "passive"))
      (node (ref "C10") (pin "1") (pinfunction "1_1") (pintype "passive"))
      (node (ref "C10") (pin "2") (pinfunction "2_2") (pintype "passive"))
      (node (ref "C11") (pin "1") (pinfunction "1_1") (pintype "passive"))
      (node (ref "C11") (pin "2") (pinfunction "2_2") (pintype "passive"))
      (node (ref "C12") (pin "1") (pinfunction "1_1") (pintype "passive"))
      (node (ref "C12") (pin "2") (pinfunction "2_2") (pintype "passive"))
      (node (ref "C17") (pin "1") (pinfunction "1_1") (pintype "passive"))
      (node (ref "C17") (pin "2") (pinfunction "2_2") (pintype "passive"))
      (node (ref "C18") (pin "1") (pinfunction "1_1") (pintype "passive"))
      (node (ref "C18") (pin "2") (pinfunction "2_2") (pintype "passive"))
      (node (ref "C19") (pin "1") (pinfunction "1_1") (pintype "passive"))
      (node (ref "C19") (pin "2") (pinfunction "2_2") (pintype "passive"))
      (node (ref "C2") (pin "2") (pinfunction "2_2") (pintype "passive"))
      (node (ref "C3") (pin "1") (pinfunction "1_1") (pintype "passive"))
      (node (ref "C3") (pin "2") (pinfunction "2_2") (pintype "passive"))
      (node (ref "C4") (pin "1") (pinfunction "1_1") (pintype "passive"))
      (node (ref "C4") (pin "2") (pinfunction "2_2") (pintype "passive"))
      (node (ref "C5") (pin "1") (pinfunction "1_1") (pintype "passive"))
      (node (ref "C5") (pin "2") (pinfunction "2_2") (pintype "passive"))
      (node (ref "C6") (pin "2") (pinfunction "2_2") (pintype "passive"))
      (node (ref "L1") (pin "a") (pinfunction "a_a") (pintype "passive"))
      (node (ref "L2") (pin "a") (pinfunction "a_a") (pintype "passive"))
      (node (ref "L3") (pin "a") (pinfunction "a_a") (pintype "passive"))
      (node (ref "R1") (pin "2") (pinfunction "2_2") (pintype "passive"))
      (node (ref "R17") (pin "2") (pinfunction "2_2") (pintype "passive"))
      (node (ref "R2") (pin "1") (pinfunction "1_1") (pintype "passive"))
      (node (ref "R26") (pin "2") (pinfunction "2_2") (pintype "passive"))
      (node (ref "R27") (pin "2") (pinfunction "2_2") (pintype "passive"))
      (node (ref "R28") (pin "2") (pinfunction "2_2") (pintype "passive"))
      (node (ref "R29") (pin "2") (pinfunction "2_2") (pintype "passive"))
      (node (ref "R3") (pin "2") (pinfunction "2_2") (pintype "passive"))
      (node (ref "R30") (pin "2") (pinfunction "2_2") (pintype "passive"))
      (node (ref "R31") (pin "2") (pinfunction "2_2") (pintype "passive"))
      (node (ref "R32") (pin "2") (pinfunction "2_2") (pintype "passive"))
      (node (ref "R33") (pin "2") (pinfunction "2_2") (pintype "passive"))
      (node (ref "R4") (pin "2") (pinfunction "2_2") (pintype "passive"))
      (node (ref "R5") (pin "1") (pinfunction "1_1") (pintype "passive"))
      (node (ref "R6") (pin "2") (pinfunction "2_2") (pintype "passive"))
      (node (ref "R7") (pin "2") (pinfunction "2_2") (pintype "passive"))
      (node (ref "R8") (pin "1") (pinfunction "1_1") (pintype "passive"))
      (node (ref "R9") (pin "2") (pinfunction "2_2") (pintype "passive"))
      (node (ref "U1") (pin "2") (pinfunction "GND_2") (pintype "passive"))
      (node (ref "U1") (pin "5") (pinfunction "VOS_5") (pintype "passive"))
      (node (ref "U1") (pin "8") (pinfunction "VIN_8") (pintype "passive"))
      (node (ref "U1") (pin "9") (pinfunction "EPAD_9") (pintype "passive"))
      (node (ref "U2") (pin "2") (pinfunction "GND_2") (pintype "passive"))
      (node (ref "U2") (pin "5") (pinfunction "VOS_5") (pintype "passive"))
      (node (ref "U2") (pin "8") (pinfunction "VIN_8") (pintype "passive"))
      (node (ref "U2") (pin "9") (pinfunction "EPAD_9") (pintype "passive"))
      (node (ref "U3") (pin "2") (pinfunction "GND_2") (pintype "passive"))
      (node (ref "U3") (pin "5") (pinfunction "VOS_5") (pintype "passive"))
      (node (ref "U3") (pin "8") (pinfunction "VIN_8") (pintype "passive"))
      (node (ref "U3") (pin "9") (pinfunction "EPAD_9") (pintype "passive"))
      (node (ref "U8") (pin "3") (pinfunction "GND1_3") (pintype "passive"))
      (node (ref "U8") (pin "8") (pinfunction "GND2_8") (pintype "passive"))
    )
    (net (code "21") (name "Net-(U1-MODE)") (class "Default")
      (node (ref "R26") (pin "1") (pinfunction "1_1") (pintype "passive"))
      (node (ref "U1") (pin "3") (pinfunction "MODE_3") (pintype "passive"))
    )
    (net (code "22") (name "Net-(U2-MODE)") (class "Default")
      (node (ref "R4") (pin "1") (pinfunction "1_1") (pintype "passive"))
      (node (ref "U2") (pin "3") (pinfunction "MODE_3") (pintype "passive"))
    )
    (net (code "23") (name "Net-(U3-MODE)") (class "Default")
      (node (ref "R1") (pin "1") (pinfunction "1_1") (pintype "passive"))
      (node (ref "U3") (pin "3") (pinfunction "MODE_3") (pintype "passive"))
    )
    (net (code "24") (name "unconnected-(C7-Pad1)") (class "Default")
      (node (ref "C7") (pin "1") (pinfunction "1_1") (pintype "passive"))
    )
    (net (code "25") (name "unconnected-(C7-Pad2)") (class "Default")
      (node (ref "C7") (pin "2") (pinfunction "2_2") (pintype "passive"))
    )
    (net (code "26") (name "unconnected-(C8-Pad1)") (class "Default")
      (node (ref "C8") (pin "1") (pinfunction "1_1") (pintype "passive"))
    )
    (net (code "27") (name "unconnected-(C8-Pad2)") (class "Default")
      (node (ref "C8") (pin "2") (pinfunction "2_2") (pintype "passive"))
    )
    (net (code "28") (name "unconnected-(C9-Pad1)") (class "Default")
      (node (ref "C9") (pin "1") (pinfunction "1_1") (pintype "passive"))
    )
    (net (code "29") (name "unconnected-(C9-Pad2)") (class "Default")
      (node (ref "C9") (pin "2") (pinfunction "2_2") (pintype "passive"))
    )
    (net (code "30") (name "unconnected-(C13-Pad1)") (class "Default")
      (node (ref "C13") (pin "1") (pinfunction "1_1") (pintype "passive"))
    )
    (net (code "31") (name "unconnected-(C13-Pad2)") (class "Default")
      (node (ref "C13") (pin "2") (pinfunction "2_2") (pintype "passive"))
    )
    (net (code "32") (name "unconnected-(C14-Pad1)") (class "Default")
      (node (ref "C14") (pin "1") (pinfunction "1_1") (pintype "passive"))
    )
    (net (code "33") (name "unconnected-(C14-Pad2)") (class "Default")
      (node (ref "C14") (pin "2") (pinfunction "2_2") (pintype "passive"))
    )
    (net (code "34") (name "unconnected-(C15-Pad1)") (class "Default")
      (node (ref "C15") (pin "1") (pinfunction "1_1") (pintype "passive"))
    )
    (net (code "35") (name "unconnected-(C15-Pad2)") (class "Default")
      (node (ref "C15") (pin "2") (pinfunction "2_2") (pintype "passive"))
    )
    (net (code "36") (name "unconnected-(C16-Pad1)") (class "Default")
      (node (ref "C16") (pin "1") (pinfunction "1_1") (pintype "passive"))
    )
    (net (code "37") (name "unconnected-(C16-Pad2)") (class "Default")
      (node (ref "C16") (pin "2") (pinfunction "2_2") (pintype "passive"))
    )
    (net (code "38") (name "unconnected-(C20-Pad1)") (class "Default")
      (node (ref "C20") (pin "1") (pinfunction "1_1") (pintype "passive"))
    )
    (net (code "39") (name "unconnected-(C20-Pad2)") (class "Default")
      (node (ref "C20") (pin "2") (pinfunction "2_2") (pintype "passive"))
    )
    (net (code "40") (name "unconnected-(U1-EN-Pad1)") (class "Default")
      (node (ref "U1") (pin "1") (pinfunction "EN_1") (pintype "passive"))
    )
    (net (code "41") (name "unconnected-(U1-PG-Pad6)") (class "Default")
      (node (ref "U1") (pin "6") (pinfunction "PG_6") (pintype "passive"))
    )
    (net (code "42") (name "unconnected-(U2-EN-Pad1)") (class "Default")
      (node (ref "U2") (pin "1") (pinfunction "EN_1") (pintype "passive"))
    )
    (net (code "43") (name "unconnected-(U2-PG-Pad6)") (class "Default")
      (node (ref "U2") (pin "6") (pinfunction "PG_6") (pintype "passive"))
    )
    (net (code "44") (name "unconnected-(U3-EN-Pad1)") (class "Default")
      (node (ref "U3") (pin "1") (pinfunction "EN_1") (pintype "passive"))
    )
    (net (code "45") (name "unconnected-(U3-PG-Pad6)") (class "Default")
      (node (ref "U3") (pin "6") (pinfunction "PG_6") (pintype "passive"))
    )
    (net (code "46") (name "unconnected-(U8-IOC1-Pad1)") (class "Default")
      (node (ref "U8") (pin "1") (pinfunction "IOC1_1") (pintype "passive"))
    )
    (net (code "47") (name "unconnected-(U8-IOC2-Pad2)") (class "Default")
      (node (ref "U8") (pin "2") (pinfunction "IOC2_2") (pintype "passive"))
    )
    (net (code "48") (name "unconnected-(U8-IOS1-Pad10)") (class "Default")
      (node (ref "U8") (pin "10") (pinfunction "IOS1_10") (pintype "passive"))
    )
    (net (code "49") (name "unconnected-(U8-IOS2-Pad9)") (class "Default")
      (node (ref "U8") (pin "9") (pinfunction "IOS2_9") (pintype "passive"))
    )
  )
)
